# minimal-arduino-uno-rev3-02-th.net
KiCad netlist of a schematic drawn in EAGLE
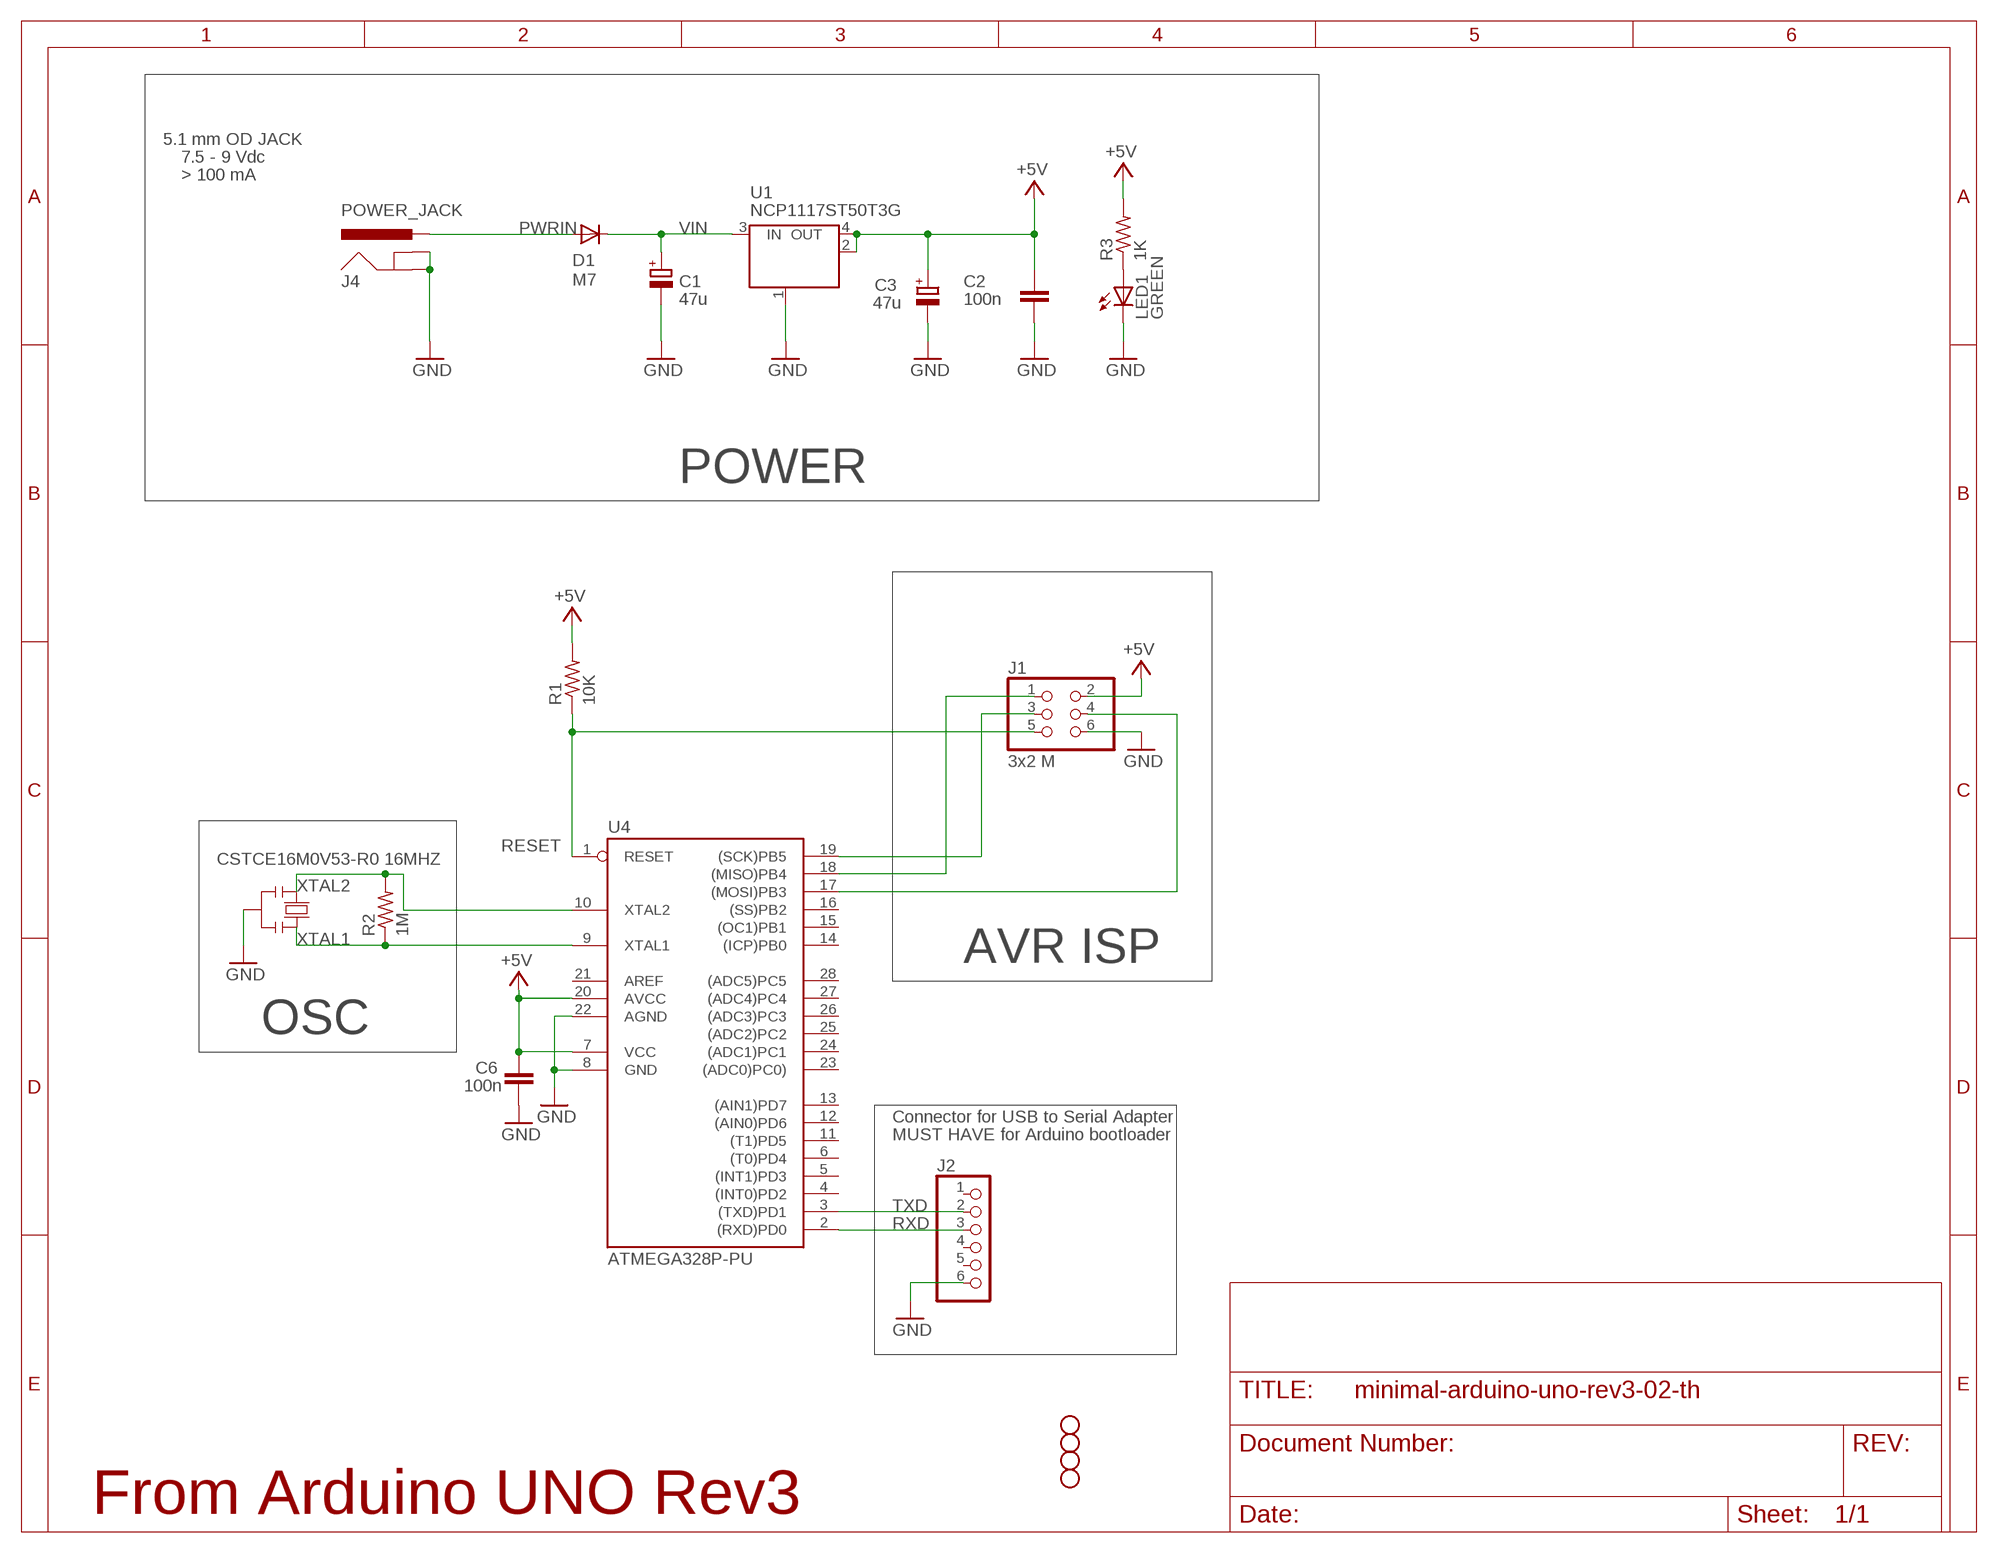
[diagram p0: schematic, sheet 1]

(export (version "E")
  (design (tool "Eeschema 10.0.6"))
  (components
    (comp (ref "C1")
      (value "47u")
      (footprint "eagle-import:PANASONIC_D")
      (libsource (lib "eagle-import") (part "CPOL-EUD"))
    )
    (comp (ref "C2")
      (value "100n")
      (footprint "eagle-import:C0805")
      (libsource (lib "eagle-import") (part "C-EUC0805"))
    )
    (comp (ref "C3")
      (value "47u")
      (footprint "eagle-import:PANASONIC_D")
      (libsource (lib "eagle-import") (part "CPOL-EUD"))
    )
    (comp (ref "C6")
      (value "100n")
      (footprint "eagle-import:C0805")
      (libsource (lib "eagle-import") (part "C-EUC0805"))
    )
    (comp (ref "D1")
      (value "M7")
      (footprint "eagle-import:SMB")
      (libsource (lib "eagle-import") (part "DIODE-SMB"))
    )
    (comp (ref "H1")
      (value "STAND-OFF")
      (footprint "eagle-import:STAND-OFF")
      (libsource (lib "eagle-import") (part "STAND-OFF"))
    )
    (comp (ref "H2")
      (value "STAND-OFF")
      (footprint "eagle-import:STAND-OFF")
      (libsource (lib "eagle-import") (part "STAND-OFF"))
    )
    (comp (ref "H3")
      (value "STAND-OFF")
      (footprint "eagle-import:STAND-OFF")
      (libsource (lib "eagle-import") (part "STAND-OFF"))
    )
    (comp (ref "H4")
      (value "STAND-OFF")
      (footprint "eagle-import:STAND-OFF")
      (libsource (lib "eagle-import") (part "STAND-OFF"))
    )
    (comp (ref "J1")
      (value "3x2 M")
      (footprint "eagle-import:2X03")
      (libsource (lib "eagle-import") (part "PINHD-2X3"))
    )
    (comp (ref "J2")
      (value "PINHD-1X6")
      (footprint "eagle-import:1X06")
      (libsource (lib "eagle-import") (part "PINHD-1X6"))
    )
    (comp (ref "J4")
      (value "POWER_JACK")
      (footprint "eagle-import:POWER_JACK_PTH")
      (libsource (lib "eagle-import") (part "POWER_JACK"))
    )
    (comp (ref "LED1")
      (value "GREEN")
      (footprint "eagle-import:CHIP-LED0805")
      (libsource (lib "eagle-import") (part "LEDCHIP-LED0805"))
    )
    (comp (ref "R1")
      (value "10K")
      (footprint "eagle-import:R0805")
      (libsource (lib "eagle-import") (part "R-US_R0805"))
    )
    (comp (ref "R2")
      (value "1M")
      (footprint "eagle-import:R0805")
      (libsource (lib "eagle-import") (part "R-US_R0805"))
    )
    (comp (ref "R3")
      (value "1K")
      (footprint "eagle-import:R0805")
      (libsource (lib "eagle-import") (part "R-US_R0805"))
    )
    (comp (ref "U1")
      (value "NCP1117ST50T3G")
      (footprint "eagle-import:SOT223")
      (libsource (lib "eagle-import") (part "MC33269ST-3.3T3"))
    )
    (comp (ref "U4")
      (value "ATMEGA328P-PU")
      (footprint "eagle-import:DIL28-3")
      (libsource (lib "eagle-import") (part "ATMEGA328P-PU"))
    )
    (comp (ref "X1")
      (value "CSTCE16M0V53-R0 16MHZ")
      (footprint "eagle-import:RESONATOR")
      (libsource (lib "eagle-import") (part "RESONATORMU"))
    )
  )
  (nets
    (net (code "1") (name "+5V") (class "Default")
      (node (ref "C2") (pin "2") (pinfunction "2_2") (pintype "passive"))
      (node (ref "C3") (pin "+") (pinfunction "+_+") (pintype "passive"))
      (node (ref "C6") (pin "2") (pinfunction "2_2") (pintype "passive"))
      (node (ref "J1") (pin "2") (pinfunction "2_2") (pintype "passive"))
      (node (ref "R1") (pin "2") (pinfunction "2_2") (pintype "passive"))
      (node (ref "R3") (pin "2") (pinfunction "2_2") (pintype "passive"))
      (node (ref "U1") (pin "2") (pinfunction "OUT_2") (pintype "passive"))
      (node (ref "U1") (pin "4") (pinfunction "OUT_4") (pintype "passive"))
      (node (ref "U4") (pin "20") (pinfunction "AVCC_20") (pintype "power_in"))
      (node (ref "U4") (pin "7") (pinfunction "VCC_7") (pintype "power_in"))
    )
    (net (code "2") (name "/PWRIN") (class "Default")
      (node (ref "D1") (pin "A") (pinfunction "A_A") (pintype "passive"))
      (node (ref "J4") (pin "PWR") (pinfunction "PWR_PWR") (pintype "bidirectional"))
    )
    (net (code "3") (name "/RESET") (class "Default")
      (node (ref "J1") (pin "5") (pinfunction "5_5") (pintype "passive"))
      (node (ref "R1") (pin "1") (pinfunction "1_1") (pintype "passive"))
      (node (ref "U4") (pin "1") (pinfunction "RESET_1") (pintype "input"))
    )
    (net (code "4") (name "/RXD") (class "Default")
      (node (ref "J2") (pin "3") (pinfunction "3_3") (pintype "passive"))
      (node (ref "U4") (pin "2") (pinfunction "(RXD)PD0_2") (pintype "bidirectional"))
    )
    (net (code "5") (name "/TXD") (class "Default")
      (node (ref "J2") (pin "2") (pinfunction "2_2") (pintype "passive"))
      (node (ref "U4") (pin "3") (pinfunction "(TXD)PD1_3") (pintype "bidirectional"))
    )
    (net (code "6") (name "/VIN") (class "Default")
      (node (ref "C1") (pin "+") (pinfunction "+_+") (pintype "passive"))
      (node (ref "D1") (pin "C") (pinfunction "C_C") (pintype "passive"))
      (node (ref "U1") (pin "3") (pinfunction "IN_3") (pintype "input"))
    )
    (net (code "7") (name "/XTAL1") (class "Default")
      (node (ref "R2") (pin "1") (pinfunction "1_1") (pintype "passive"))
      (node (ref "U4") (pin "9") (pinfunction "XTAL1_9") (pintype "bidirectional"))
      (node (ref "X1") (pin "3") (pinfunction "3_3") (pintype "passive"))
    )
    (net (code "8") (name "/XTAL2") (class "Default")
      (node (ref "R2") (pin "2") (pinfunction "2_2") (pintype "passive"))
      (node (ref "U4") (pin "10") (pinfunction "XTAL2_10") (pintype "bidirectional"))
      (node (ref "X1") (pin "1") (pinfunction "1_1") (pintype "passive"))
    )
    (net (code "9") (name "GND") (class "Default")
      (node (ref "C1") (pin "-") (pinfunction "-_-") (pintype "passive"))
      (node (ref "C2") (pin "1") (pinfunction "1_1") (pintype "passive"))
      (node (ref "C3") (pin "-") (pinfunction "-_-") (pintype "passive"))
      (node (ref "C6") (pin "1") (pinfunction "1_1") (pintype "passive"))
      (node (ref "J1") (pin "6") (pinfunction "6_6") (pintype "passive"))
      (node (ref "J2") (pin "6") (pinfunction "6_6") (pintype "passive"))
      (node (ref "J4") (pin "GND") (pinfunction "GND_GND") (pintype "bidirectional"))
      (node (ref "J4") (pin "GNDBREAK") (pinfunction "GNDBREAK_GNDBREAK") (pintype "bidirectional"))
      (node (ref "LED1") (pin "C") (pinfunction "C_C") (pintype "passive"))
      (node (ref "U1") (pin "1") (pinfunction "GND/ADJ_1") (pintype "input"))
      (node (ref "U4") (pin "22") (pinfunction "AGND_22") (pintype "power_in"))
      (node (ref "U4") (pin "8") (pinfunction "GND_8") (pintype "power_in"))
      (node (ref "X1") (pin "2") (pinfunction "2_2") (pintype "passive"))
    )
    (net (code "10") (name "Net-(LED1-PadA)") (class "Default")
      (node (ref "LED1") (pin "A") (pinfunction "A_A") (pintype "passive"))
      (node (ref "R3") (pin "1") (pinfunction "1_1") (pintype "passive"))
    )
    (net (code "11") (name "Net-(U4-(MISO)PB4)") (class "Default")
      (node (ref "J1") (pin "1") (pinfunction "1_1") (pintype "passive"))
      (node (ref "U4") (pin "18") (pinfunction "(MISO)PB4_18") (pintype "bidirectional"))
    )
    (net (code "12") (name "Net-(U4-(MOSI)PB3)") (class "Default")
      (node (ref "J1") (pin "4") (pinfunction "4_4") (pintype "passive"))
      (node (ref "U4") (pin "17") (pinfunction "(MOSI)PB3_17") (pintype "bidirectional"))
    )
    (net (code "13") (name "Net-(U4-(SCK)PB5)") (class "Default")
      (node (ref "J1") (pin "3") (pinfunction "3_3") (pintype "passive"))
      (node (ref "U4") (pin "19") (pinfunction "(SCK)PB5_19") (pintype "bidirectional"))
    )
    (net (code "14") (name "unconnected-(J2-Pad1)") (class "Default")
      (node (ref "J2") (pin "1") (pinfunction "1_1") (pintype "passive"))
    )
    (net (code "15") (name "unconnected-(J2-Pad4)") (class "Default")
      (node (ref "J2") (pin "4") (pinfunction "4_4") (pintype "passive"))
    )
    (net (code "16") (name "unconnected-(J2-Pad5)") (class "Default")
      (node (ref "J2") (pin "5") (pinfunction "5_5") (pintype "passive"))
    )
    (net (code "17") (name "unconnected-(U4-(ADC0)PC0)-Pad23)") (class "Default")
      (node (ref "U4") (pin "23") (pinfunction "(ADC0)PC0)_23") (pintype "bidirectional"))
    )
    (net (code "18") (name "unconnected-(U4-(ADC1)PC1-Pad24)") (class "Default")
      (node (ref "U4") (pin "24") (pinfunction "(ADC1)PC1_24") (pintype "bidirectional"))
    )
    (net (code "19") (name "unconnected-(U4-(ADC2)PC2-Pad25)") (class "Default")
      (node (ref "U4") (pin "25") (pinfunction "(ADC2)PC2_25") (pintype "bidirectional"))
    )
    (net (code "20") (name "unconnected-(U4-(ADC3)PC3-Pad26)") (class "Default")
      (node (ref "U4") (pin "26") (pinfunction "(ADC3)PC3_26") (pintype "bidirectional"))
    )
    (net (code "21") (name "unconnected-(U4-(ADC4)PC4-Pad27)") (class "Default")
      (node (ref "U4") (pin "27") (pinfunction "(ADC4)PC4_27") (pintype "bidirectional"))
    )
    (net (code "22") (name "unconnected-(U4-(ADC5)PC5-Pad28)") (class "Default")
      (node (ref "U4") (pin "28") (pinfunction "(ADC5)PC5_28") (pintype "bidirectional"))
    )
    (net (code "23") (name "unconnected-(U4-(AIN0)PD6-Pad12)") (class "Default")
      (node (ref "U4") (pin "12") (pinfunction "(AIN0)PD6_12") (pintype "bidirectional"))
    )
    (net (code "24") (name "unconnected-(U4-(AIN1)PD7-Pad13)") (class "Default")
      (node (ref "U4") (pin "13") (pinfunction "(AIN1)PD7_13") (pintype "bidirectional"))
    )
    (net (code "25") (name "unconnected-(U4-(ICP)PB0-Pad14)") (class "Default")
      (node (ref "U4") (pin "14") (pinfunction "(ICP)PB0_14") (pintype "bidirectional"))
    )
    (net (code "26") (name "unconnected-(U4-(INT0)PD2-Pad4)") (class "Default")
      (node (ref "U4") (pin "4") (pinfunction "(INT0)PD2_4") (pintype "bidirectional"))
    )
    (net (code "27") (name "unconnected-(U4-(INT1)PD3-Pad5)") (class "Default")
      (node (ref "U4") (pin "5") (pinfunction "(INT1)PD3_5") (pintype "bidirectional"))
    )
    (net (code "28") (name "unconnected-(U4-(OC1)PB1-Pad15)") (class "Default")
      (node (ref "U4") (pin "15") (pinfunction "(OC1)PB1_15") (pintype "bidirectional"))
    )
    (net (code "29") (name "unconnected-(U4-(SS)PB2-Pad16)") (class "Default")
      (node (ref "U4") (pin "16") (pinfunction "(SS)PB2_16") (pintype "bidirectional"))
    )
    (net (code "30") (name "unconnected-(U4-(T0)PD4-Pad6)") (class "Default")
      (node (ref "U4") (pin "6") (pinfunction "(T0)PD4_6") (pintype "bidirectional"))
    )
    (net (code "31") (name "unconnected-(U4-(T1)PD5-Pad11)") (class "Default")
      (node (ref "U4") (pin "11") (pinfunction "(T1)PD5_11") (pintype "bidirectional"))
    )
    (net (code "32") (name "unconnected-(U4-AREF-Pad21)") (class "Default")
      (node (ref "U4") (pin "21") (pinfunction "AREF_21") (pintype "passive"))
    )
  )
)
